# Wash_Hand.net
KiCad netlist of a schematic drawn in EAGLE
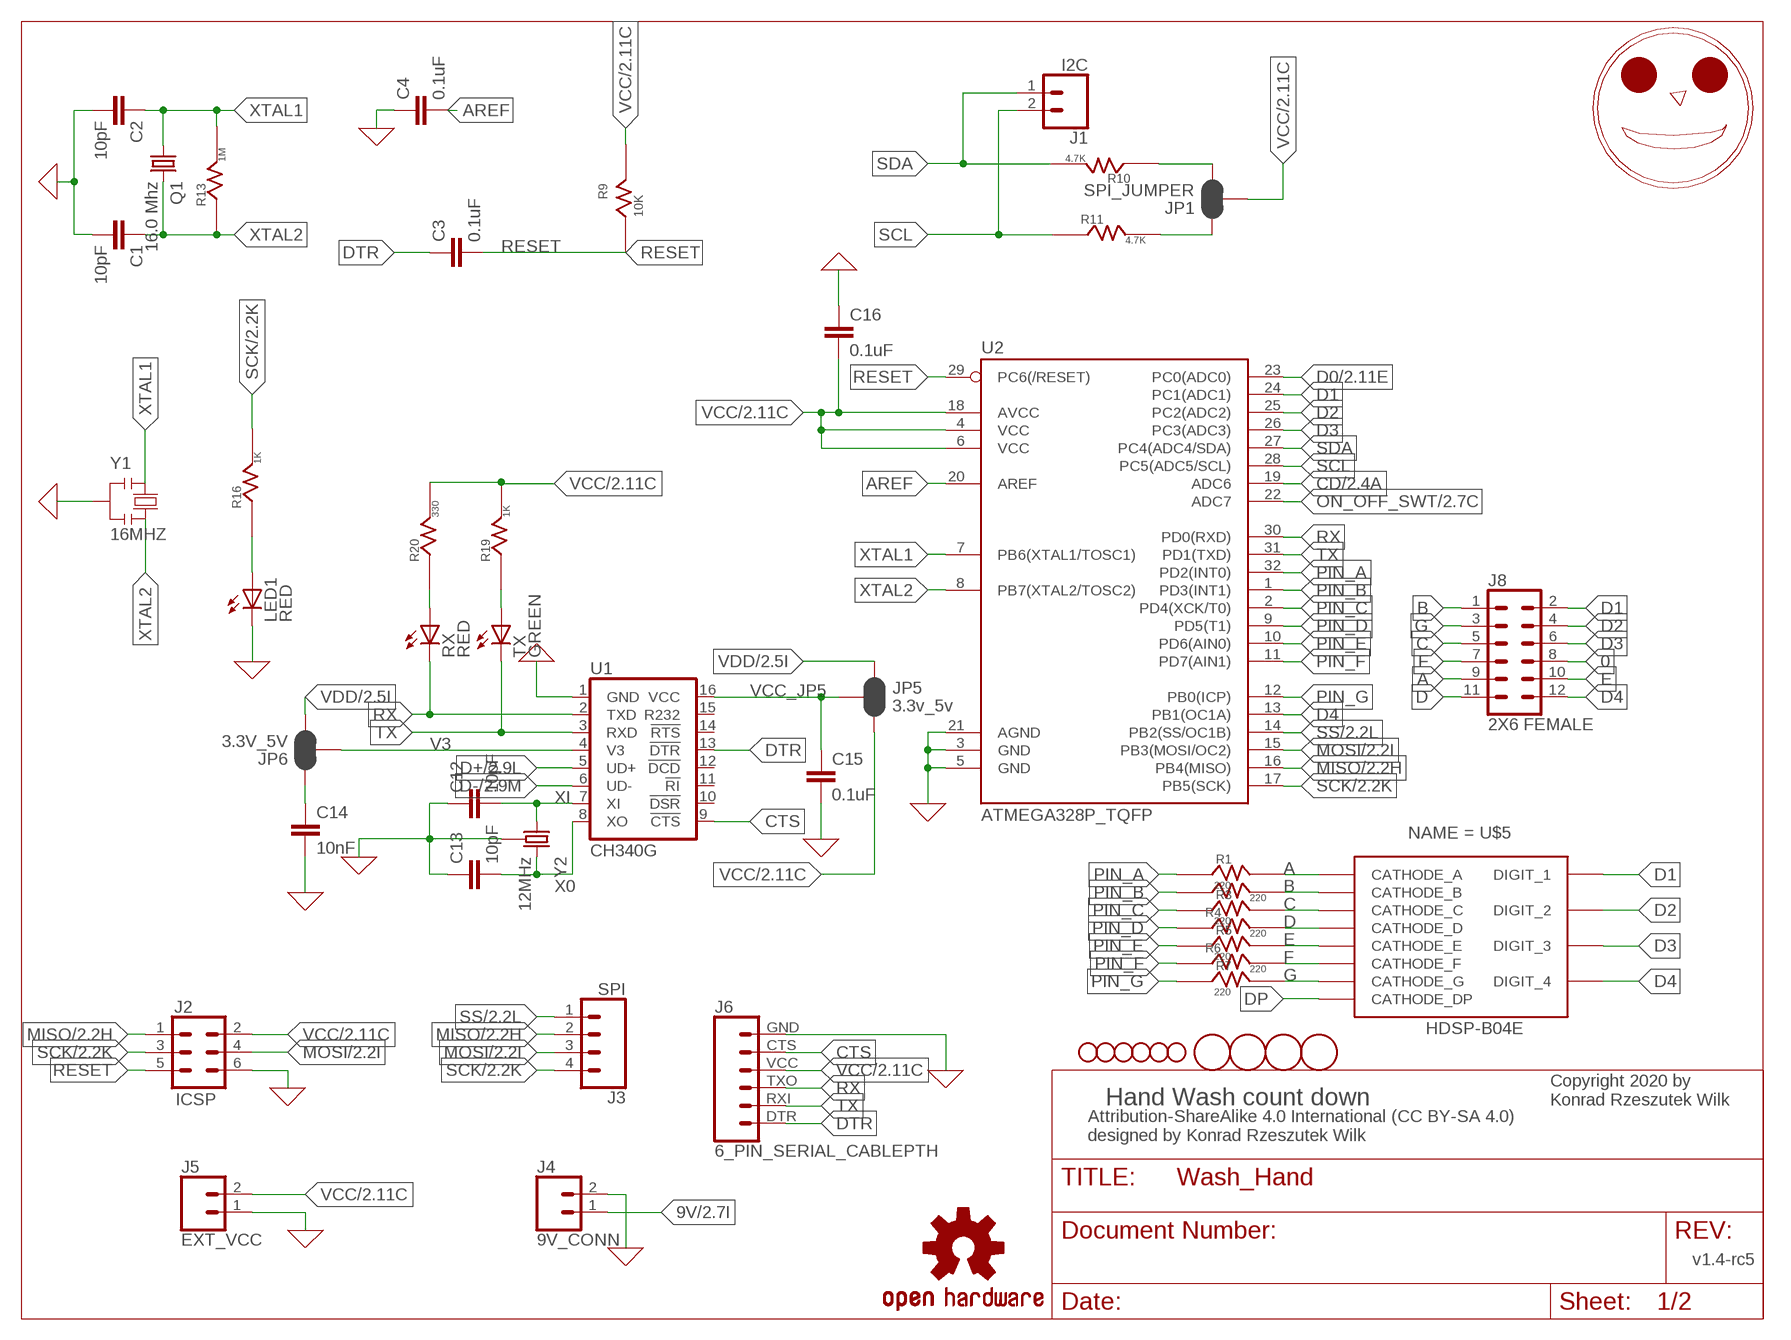
[diagram p0: schematic, sheet 1]
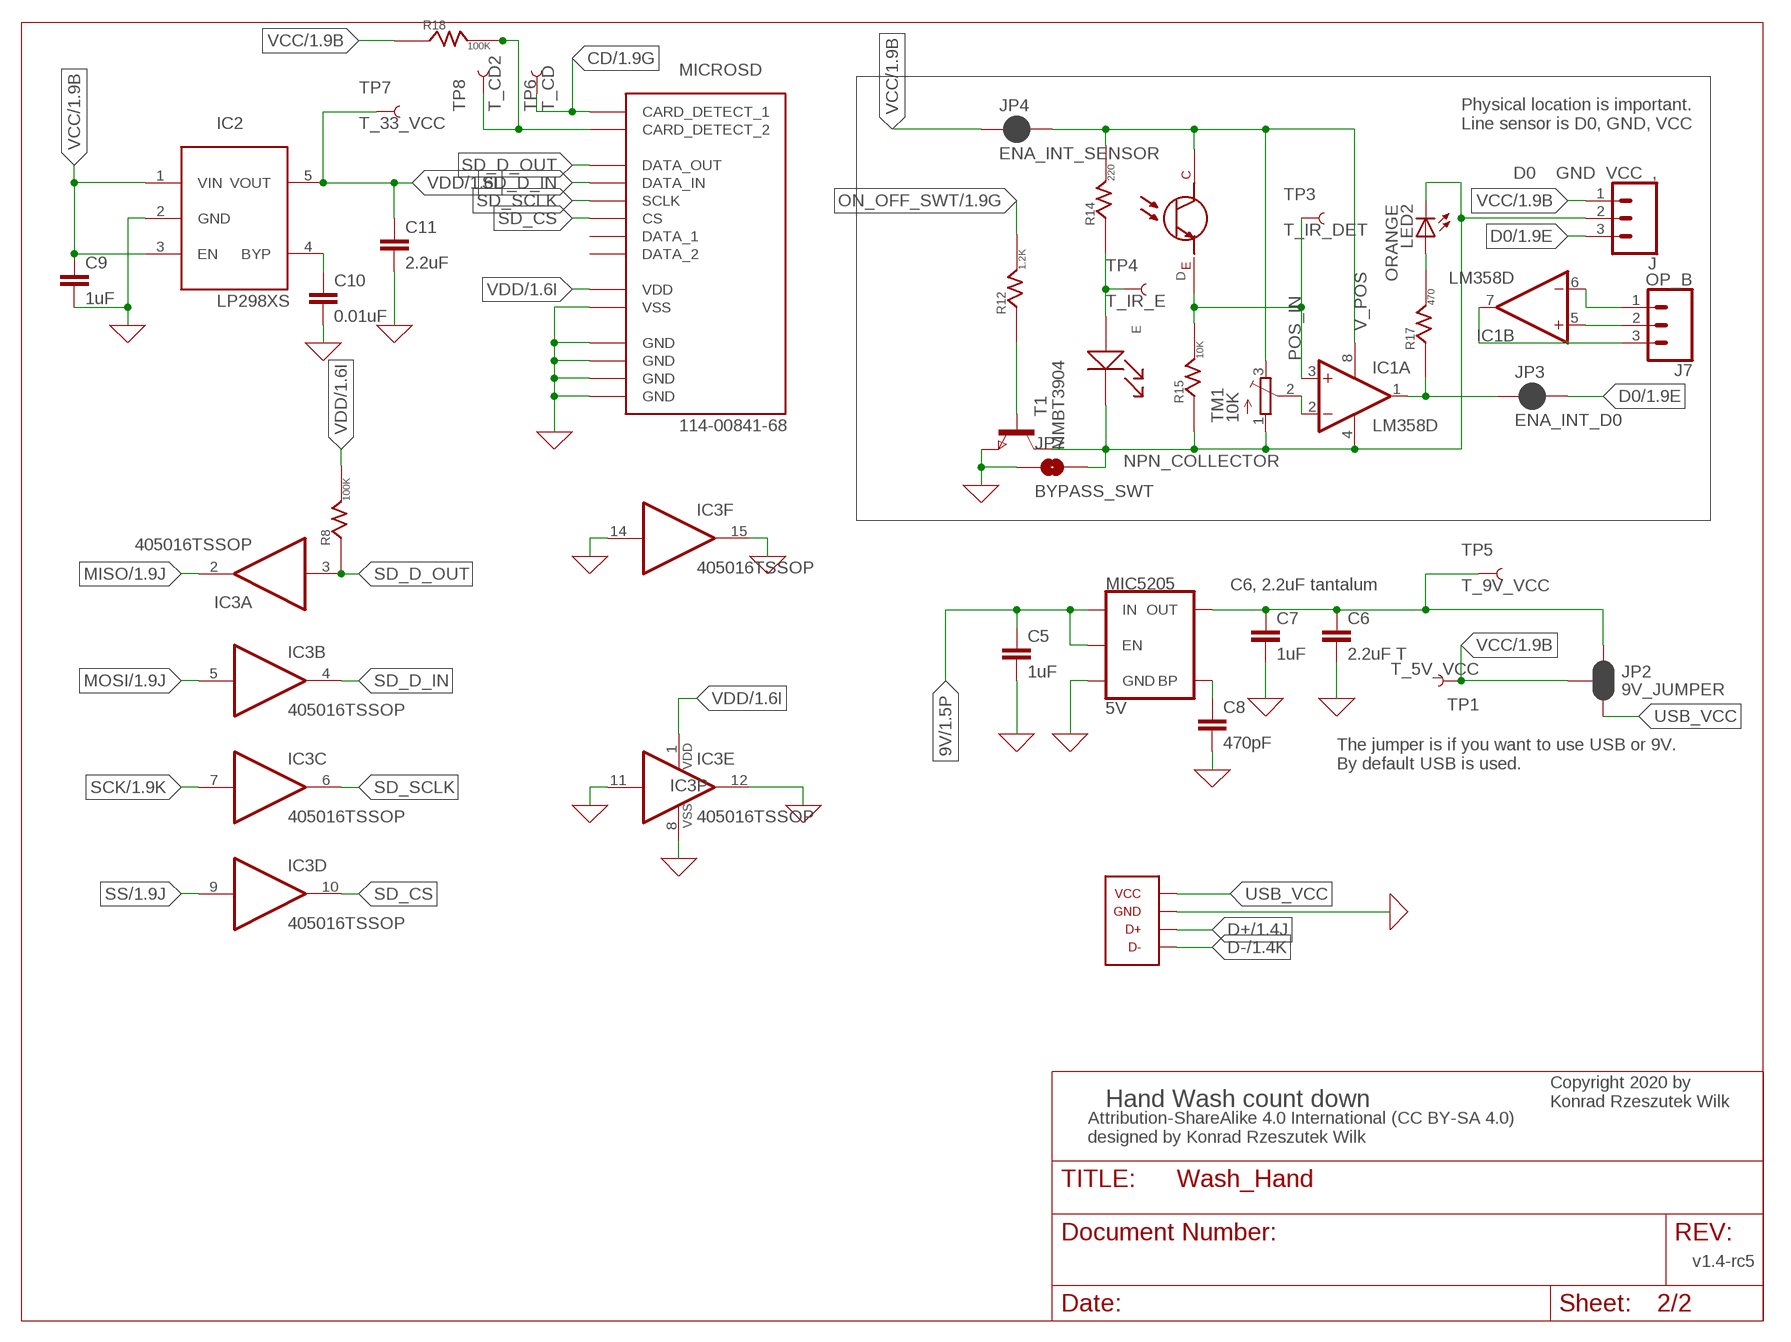
[diagram p1: schematic, sheet 2]

(export (version "E")
  (design (tool "Eeschema 10.0.6"))
  (components
    (comp (ref "C5")
      (value "1uF")
      (footprint "eagle-import:1206")
      (libsource (lib "eagle-import") (part "1.0UF-1206-50V-10%"))
    )
    (comp (ref "C6")
      (value "2.2uF T")
      (footprint "eagle-import:1206")
      (libsource (lib "eagle-import") (part "1.0UF-1206-50V-10%"))
    )
    (comp (ref "C7")
      (value "1uF")
      (footprint "eagle-import:1206")
      (libsource (lib "eagle-import") (part "1.0UF-1206-50V-10%"))
    )
    (comp (ref "C8")
      (value "470pF")
      (footprint "eagle-import:1206")
      (libsource (lib "eagle-import") (part "1.0UF-1206-50V-10%"))
    )
    (comp (ref "C9")
      (value "1uF")
      (footprint "eagle-import:1206")
      (libsource (lib "eagle-import") (part "1.0UF-1206-50V-10%"))
    )
    (comp (ref "C10")
      (value "0.01uF")
      (footprint "eagle-import:1206")
      (libsource (lib "eagle-import") (part "1.0UF-1206-50V-10%"))
    )
    (comp (ref "C11")
      (value "2.2uF")
      (footprint "eagle-import:1206")
      (libsource (lib "eagle-import") (part "1.0UF-1206-50V-10%"))
    )
    (comp (ref "D")
      (value "LTR-301")
      (footprint "eagle-import:LTR-301")
      (libsource (lib "eagle-import") (part "LTR-301"))
    )
    (comp (ref "E")
      (value "LTE-302")
      (footprint "eagle-import:LTE-302")
      (libsource (lib "eagle-import") (part "LTE-302"))
    )
    (comp (ref "IC1")
      (value "LM358D")
      (footprint "eagle-import:SO08")
      (libsource (lib "eagle-import") (part "LM358D"))
    )
    (comp (ref "IC2")
      (value "LP298XS")
      (footprint "eagle-import:SOT23-5L")
      (libsource (lib "eagle-import") (part "LP298XS"))
    )
    (comp (ref "IC3")
      (value "405016TSSOP")
      (footprint "eagle-import:TSSOP16")
      (libsource (lib "eagle-import") (part "405016TSSOP"))
    )
    (comp (ref "J")
      (value "D0 GND VCC ,")
      (footprint "eagle-import:1X03")
      (libsource (lib "eagle-import") (part "CONN_03"))
    )
    (comp (ref "J7")
      (value "OP_B")
      (footprint "eagle-import:1X03")
      (libsource (lib "eagle-import") (part "CONN_03"))
    )
    (comp (ref "JP2")
      (value "9V_JUMPER")
      (footprint "eagle-import:SMT-JUMPER_3_2-NC_PASTE_SILK")
      (libsource (lib "eagle-import") (part "JUMPER-SMT_3_2-NC_PASTE_SILK"))
    )
    (comp (ref "JP3")
      (value "ENA_INT_D0")
      (footprint "eagle-import:SMT-JUMPER_2_NC_PASTE_SILK")
      (libsource (lib "eagle-import") (part "JUMPER-SMT_2_NC_PASTE_SILK"))
    )
    (comp (ref "JP4")
      (value "ENA_INT_SENSOR")
      (footprint "eagle-import:SMT-JUMPER_2_NC_PASTE_SILK")
      (libsource (lib "eagle-import") (part "JUMPER-SMT_2_NC_PASTE_SILK"))
    )
    (comp (ref "JP7")
      (value "BYPASS_SWT")
      (footprint "eagle-import:SMT-JUMPER_2_NO_SILK")
      (libsource (lib "eagle-import") (part "JUMPER-SMT_2_NO_SILK"))
    )
    (comp (ref "LED2")
      (value "ORANGE")
      (footprint "eagle-import:1206")
      (libsource (lib "eagle-import") (part "LEDSMT1206"))
    )
    (comp (ref "MIC5205")
      (value "5V")
      (footprint "eagle-import:SOT23-5")
      (libsource (lib "eagle-import") (part "V_REG_MIC52055V"))
    )
    (comp (ref "MICROSD")
      (value "114-00841-68")
      (footprint "eagle-import:114-00841-68")
      (libsource (lib "eagle-import") (part "114-00841-68"))
    )
    (comp (ref "R8")
      (value "100K")
      (footprint "eagle-import:1206")
      (libsource (lib "eagle-import") (part "RESISTORR1206"))
    )
    (comp (ref "R12")
      (value "1.2K")
      (footprint "eagle-import:1206")
      (libsource (lib "eagle-import") (part "RESISTORR1206"))
    )
    (comp (ref "R14")
      (value "220")
      (footprint "eagle-import:1206")
      (libsource (lib "eagle-import") (part "RESISTORR1206"))
    )
    (comp (ref "R15")
      (value "10K")
      (footprint "eagle-import:1206")
      (libsource (lib "eagle-import") (part "RESISTORR1206"))
    )
    (comp (ref "R17")
      (value "470")
      (footprint "eagle-import:1206")
      (libsource (lib "eagle-import") (part "RESISTORR1206"))
    )
    (comp (ref "R18")
      (value "100K")
      (footprint "eagle-import:1206")
      (libsource (lib "eagle-import") (part "RESISTORR1206"))
    )
    (comp (ref "T1")
      (value "MMBT3904")
      (footprint "eagle-import:SOT-23")
      (fields (field (name "MPN") "DSS20201L-7"))
      (libsource (lib "eagle-import") (part "NPNSOT23"))
    )
    (comp (ref "TM1")
      (value "10K")
      (footprint "eagle-import:TC33X")
      (libsource (lib "eagle-import") (part "TRIMPOTTC33X"))
    )
    (comp (ref "TP1")
      (value "T_5V_VCC")
      (footprint "eagle-import:PAD.03X.04")
      (libsource (lib "eagle-import") (part "TEST-POINT3X4"))
    )
    (comp (ref "TP3")
      (value "T_IR_DET")
      (footprint "eagle-import:PAD.03X.04")
      (libsource (lib "eagle-import") (part "TEST-POINT3X4"))
    )
    (comp (ref "TP4")
      (value "T_IR_E")
      (footprint "eagle-import:PAD.03X.04")
      (libsource (lib "eagle-import") (part "TEST-POINT3X4"))
    )
    (comp (ref "TP5")
      (value "T_9V_VCC")
      (footprint "eagle-import:PAD.03X.04")
      (libsource (lib "eagle-import") (part "TEST-POINT3X4"))
    )
    (comp (ref "TP6")
      (value "T_CD")
      (footprint "eagle-import:PAD.03X.04")
      (libsource (lib "eagle-import") (part "TEST-POINT3X4"))
    )
    (comp (ref "TP7")
      (value "T_33_VCC")
      (footprint "eagle-import:PAD.03X.04")
      (libsource (lib "eagle-import") (part "TEST-POINT3X4"))
    )
    (comp (ref "TP8")
      (value "T_CD2")
      (footprint "eagle-import:PAD.03X.04")
      (libsource (lib "eagle-import") (part "TEST-POINT3X4"))
    )
    (comp (ref "U$4")
      (value "USB_MICROB_10118194_AMPHENOL")
      (footprint "eagle-import:USB_MICROB_10118194_AMPHENOL")
      (libsource (lib "eagle-import") (part "USB_MICROB_10118194_AMPHENOL"))
    )
    (comp (ref "C1")
      (value "10pF")
      (footprint "eagle-import:1206")
      (libsource (lib "eagle-import") (part "10UF-1206-6.3V-20%"))
    )
    (comp (ref "C2")
      (value "10pF")
      (footprint "eagle-import:1206")
      (libsource (lib "eagle-import") (part "10UF-1206-6.3V-20%"))
    )
    (comp (ref "C3")
      (value "0.1uF")
      (footprint "eagle-import:1206")
      (libsource (lib "eagle-import") (part "1.0UF-1206-50V-10%"))
    )
    (comp (ref "C4")
      (value "0.1uF")
      (footprint "eagle-import:1206")
      (libsource (lib "eagle-import") (part "1.0UF-1206-50V-10%"))
    )
    (comp (ref "C12")
      (value "10pF")
      (footprint "eagle-import:1206")
      (libsource (lib "eagle-import") (part "10UF-1206-6.3V-20%"))
    )
    (comp (ref "C13")
      (value "10pF")
      (footprint "eagle-import:1206")
      (libsource (lib "eagle-import") (part "10UF-1206-6.3V-20%"))
    )
    (comp (ref "C14")
      (value "10nF")
      (footprint "eagle-import:1206")
      (libsource (lib "eagle-import") (part "10UF-1206-6.3V-20%"))
    )
    (comp (ref "C15")
      (value "0.1uF")
      (footprint "eagle-import:1206")
      (libsource (lib "eagle-import") (part "10UF-1206-6.3V-20%"))
    )
    (comp (ref "C16")
      (value "0.1uF")
      (footprint "eagle-import:1206")
      (libsource (lib "eagle-import") (part "10UF-1206-6.3V-20%"))
    )
    (comp (ref "H1")
      (value "STAND-OFF")
      (footprint "eagle-import:STAND-OFF")
      (libsource (lib "eagle-import") (part "STAND-OFF"))
    )
    (comp (ref "H2")
      (value "STAND-OFF")
      (footprint "eagle-import:STAND-OFF")
      (libsource (lib "eagle-import") (part "STAND-OFF"))
    )
    (comp (ref "H3")
      (value "STAND-OFF")
      (footprint "eagle-import:STAND-OFF")
      (libsource (lib "eagle-import") (part "STAND-OFF"))
    )
    (comp (ref "H4")
      (value "STAND-OFF")
      (footprint "eagle-import:STAND-OFF")
      (libsource (lib "eagle-import") (part "STAND-OFF"))
    )
    (comp (ref "H5")
      (value "STAND-OFF")
      (footprint "eagle-import:STAND-OFF")
      (libsource (lib "eagle-import") (part "STAND-OFF"))
    )
    (comp (ref "H6")
      (value "STAND-OFF")
      (footprint "eagle-import:STAND-OFF")
      (libsource (lib "eagle-import") (part "STAND-OFF"))
    )
    (comp (ref "J1")
      (value "I2C")
      (footprint "eagle-import:1X02")
      (libsource (lib "eagle-import") (part "CONN_02"))
    )
    (comp (ref "J2")
      (value "ICSP")
      (footprint "eagle-import:2X3")
      (libsource (lib "eagle-import") (part "CONN_03X2FEMALE"))
    )
    (comp (ref "J3")
      (value "SPI")
      (footprint "eagle-import:1X04")
      (libsource (lib "eagle-import") (part "CONN_04"))
    )
    (comp (ref "J4")
      (value "9V_CONN")
      (footprint "eagle-import:1X02")
      (libsource (lib "eagle-import") (part "CONN_02"))
    )
    (comp (ref "J5")
      (value "EXT_VCC")
      (footprint "eagle-import:1X02")
      (libsource (lib "eagle-import") (part "CONN_02"))
    )
    (comp (ref "J6")
      (value "6_PIN_SERIAL_CABLEPTH")
      (footprint "eagle-import:FTDI_BASIC")
      (libsource (lib "eagle-import") (part "6_PIN_SERIAL_CABLEPTH"))
    )
    (comp (ref "J8")
      (value "2X6 FEMALE")
      (footprint "eagle-import:2X6")
      (libsource (lib "eagle-import") (part "CONN_06X2PTH_FEMALE"))
    )
    (comp (ref "JP1")
      (value "SPI_JUMPER")
      (footprint "eagle-import:SMT-JUMPER_3_2-NC_PASTE_SILK")
      (libsource (lib "eagle-import") (part "JUMPER-SMT_3_2-NC_PASTE_SILK"))
    )
    (comp (ref "JP5")
      (value "3.3v_5v")
      (footprint "eagle-import:SMT-JUMPER_3_2-NC_PASTE_SILK")
      (libsource (lib "eagle-import") (part "JUMPER-SMT_3_2-NC_PASTE_SILK"))
    )
    (comp (ref "JP6")
      (value "3.3V_5V")
      (footprint "eagle-import:SMT-JUMPER_3_2-NC_PASTE_SILK")
      (libsource (lib "eagle-import") (part "JUMPER-SMT_3_2-NC_PASTE_SILK"))
    )
    (comp (ref "LED1")
      (value "RED")
      (footprint "eagle-import:1206")
      (libsource (lib "eagle-import") (part "LEDSMT1206"))
    )
    (comp (ref "LOGO1")
      (value "OSHW-LOGOM")
      (footprint "eagle-import:OSHW-LOGO-M")
      (libsource (lib "eagle-import") (part "OSHW-LOGOM"))
    )
    (comp (ref "LOGO2")
      (value "HAPPY_FACE_LOGO")
      (footprint "eagle-import:HAPPY_FACE_LOGO")
      (libsource (lib "eagle-import") (part "HAPPY_FACE_LOGO"))
    )
    (comp (ref "Q1")
      (value "16.0 Mhz")
      (footprint "eagle-import:HC49_S")
      (libsource (lib "eagle-import") (part "CRYSTALHC49S"))
    )
    (comp (ref "R1")
      (value "220")
      (footprint "eagle-import:1206")
      (libsource (lib "eagle-import") (part "RESISTORR1206"))
    )
    (comp (ref "R2")
      (value "220")
      (footprint "eagle-import:1206")
      (libsource (lib "eagle-import") (part "RESISTORR1206"))
    )
    (comp (ref "R3")
      (value "220")
      (footprint "eagle-import:1206")
      (libsource (lib "eagle-import") (part "RESISTORR1206"))
    )
    (comp (ref "R4")
      (value "220")
      (footprint "eagle-import:1206")
      (libsource (lib "eagle-import") (part "RESISTORR1206"))
    )
    (comp (ref "R5")
      (value "220")
      (footprint "eagle-import:1206")
      (libsource (lib "eagle-import") (part "RESISTORR1206"))
    )
    (comp (ref "R6")
      (value "220")
      (footprint "eagle-import:1206")
      (libsource (lib "eagle-import") (part "RESISTORR1206"))
    )
    (comp (ref "R7")
      (value "220")
      (footprint "eagle-import:1206")
      (libsource (lib "eagle-import") (part "RESISTORR1206"))
    )
    (comp (ref "R9")
      (value "10K")
      (footprint "eagle-import:1206")
      (libsource (lib "eagle-import") (part "RESISTORR1206"))
    )
    (comp (ref "R10")
      (value "4.7K")
      (footprint "eagle-import:1206")
      (libsource (lib "eagle-import") (part "RESISTORR1206"))
    )
    (comp (ref "R11")
      (value "4.7K")
      (footprint "eagle-import:1206")
      (libsource (lib "eagle-import") (part "RESISTORR1206"))
    )
    (comp (ref "R13")
      (value "1M")
      (footprint "eagle-import:1206")
      (libsource (lib "eagle-import") (part "RESISTORR1206"))
    )
    (comp (ref "R16")
      (value "1K")
      (footprint "eagle-import:1206")
      (libsource (lib "eagle-import") (part "RESISTORR1206"))
    )
    (comp (ref "R19")
      (value "1K")
      (footprint "eagle-import:1206")
      (libsource (lib "eagle-import") (part "RESISTORR1206"))
    )
    (comp (ref "R20")
      (value "330")
      (footprint "eagle-import:1206")
      (libsource (lib "eagle-import") (part "RESISTORR1206"))
    )
    (comp (ref "RX")
      (value "RED")
      (footprint "eagle-import:1206")
      (libsource (lib "eagle-import") (part "LEDSMT1206"))
    )
    (comp (ref "TX")
      (value "GREEN")
      (footprint "eagle-import:1206")
      (libsource (lib "eagle-import") (part "LEDSMT1206"))
    )
    (comp (ref "U$5")
      (value "HDSP-B04E")
      (footprint "eagle-import:HDSP-B0XE")
      (libsource (lib "eagle-import") (part "HDSP-B04E"))
    )
    (comp (ref "U$7")
      (value "FIDUCIAL")
      (footprint "eagle-import:FIDUCIAL_1MM")
      (libsource (lib "eagle-import") (part "FIDUCIAL"))
    )
    (comp (ref "U$8")
      (value "FIDUCIAL")
      (footprint "eagle-import:FIDUCIAL_1MM")
      (libsource (lib "eagle-import") (part "FIDUCIAL"))
    )
    (comp (ref "U$9")
      (value "FIDUCIAL")
      (footprint "eagle-import:FIDUCIAL_1MM")
      (libsource (lib "eagle-import") (part "FIDUCIAL"))
    )
    (comp (ref "U$10")
      (value "FIDUCIAL")
      (footprint "eagle-import:FIDUCIAL_1MM")
      (libsource (lib "eagle-import") (part "FIDUCIAL"))
    )
    (comp (ref "U1")
      (value "CH340G")
      (footprint "eagle-import:SO016")
      (libsource (lib "eagle-import") (part "CH340GSMD"))
    )
    (comp (ref "U2")
      (value "ATMEGA328P_TQFP")
      (footprint "eagle-import:TQFP32-08")
      (libsource (lib "eagle-import") (part "ATMEGA328P_TQFP"))
    )
    (comp (ref "Y1")
      (value "16MHZ")
      (footprint "eagle-import:RESONATOR")
      (libsource (lib "eagle-import") (part "RESONATORMU"))
    )
    (comp (ref "Y2")
      (value "12MHz")
      (footprint "eagle-import:CRYSTAL-SMD-3.2X2.5")
      (libsource (lib "eagle-import") (part "CRYSTAL-GROUNDED3.2X2.5"))
    )
  )
  (nets
    (net (code "1") (name "0") (class "Default")
      (node (ref "C1") (pin "2") (pinfunction "2_2") (pintype "passive"))
      (node (ref "C10") (pin "2") (pinfunction "2_2") (pintype "passive"))
      (node (ref "C11") (pin "2") (pinfunction "2_2") (pintype "passive"))
      (node (ref "C12") (pin "1") (pinfunction "1_1") (pintype "passive"))
      (node (ref "C13") (pin "1") (pinfunction "1_1") (pintype "passive"))
      (node (ref "C14") (pin "2") (pinfunction "2_2") (pintype "passive"))
      (node (ref "C15") (pin "2") (pinfunction "2_2") (pintype "passive"))
      (node (ref "C16") (pin "1") (pinfunction "1_1") (pintype "passive"))
      (node (ref "C2") (pin "2") (pinfunction "2_2") (pintype "passive"))
      (node (ref "C4") (pin "1") (pinfunction "1_1") (pintype "passive"))
      (node (ref "C5") (pin "2") (pinfunction "2_2") (pintype "passive"))
      (node (ref "C6") (pin "2") (pinfunction "2_2") (pintype "passive"))
      (node (ref "C7") (pin "2") (pinfunction "2_2") (pintype "passive"))
      (node (ref "C8") (pin "2") (pinfunction "2_2") (pintype "passive"))
      (node (ref "C9") (pin "2") (pinfunction "2_2") (pintype "passive"))
      (node (ref "IC2") (pin "2") (pinfunction "GND_2") (pintype "bidirectional"))
      (node (ref "IC3") (pin "11") (pinfunction "I_11") (pintype "input"))
      (node (ref "IC3") (pin "12") (pinfunction "O_12") (pintype "output"))
      (node (ref "IC3") (pin "14") (pinfunction "I_14") (pintype "input"))
      (node (ref "IC3") (pin "15") (pinfunction "O_15") (pintype "output"))
      (node (ref "IC3") (pin "8") (pinfunction "VSS_8") (pintype "power_in"))
      (node (ref "J2") (pin "6") (pinfunction "6_6") (pintype "bidirectional"))
      (node (ref "J4") (pin "2") (pinfunction "2_2") (pintype "passive"))
      (node (ref "J5") (pin "1") (pinfunction "1_1") (pintype "passive"))
      (node (ref "J6") (pin "GND") (pinfunction "6_GND") (pintype "passive"))
      (node (ref "J8") (pin "8") (pinfunction "8_8") (pintype "passive"))
      (node (ref "JP7") (pin "1") (pinfunction "1_1") (pintype "passive"))
      (node (ref "LED1") (pin "C") (pinfunction "C_C") (pintype "passive"))
      (node (ref "MIC5205") (pin "2") (pinfunction "GND_2") (pintype "input"))
      (node (ref "MICROSD") (pin "GND$1") (pinfunction "GND_GND$1") (pintype "power_in"))
      (node (ref "MICROSD") (pin "GND$2") (pinfunction "GND_GND$2") (pintype "power_in"))
      (node (ref "MICROSD") (pin "GND$3") (pinfunction "GND_GND$3") (pintype "power_in"))
      (node (ref "MICROSD") (pin "GND$4") (pinfunction "GND_GND$4") (pintype "power_in"))
      (node (ref "MICROSD") (pin "VSS") (pinfunction "VSS_VSS") (pintype "power_in"))
      (node (ref "T1") (pin "2") (pinfunction "E_2") (pintype "passive"))
      (node (ref "U$4") (pin "5") (pinfunction "GND_5") (pintype "bidirectional"))
      (node (ref "U1") (pin "1") (pinfunction "GND_1") (pintype "bidirectional"))
      (node (ref "U2") (pin "21") (pinfunction "AGND_21") (pintype "bidirectional"))
      (node (ref "U2") (pin "3") (pinfunction "GND_3") (pintype "bidirectional"))
      (node (ref "U2") (pin "5") (pinfunction "GND_5") (pintype "bidirectional"))
      (node (ref "Y1") (pin "2") (pinfunction "2_2") (pintype "passive"))
      (node (ref "Y2") (pin "2") (pinfunction "GND_2") (pintype "passive"))
      (node (ref "Y2") (pin "4") (pinfunction "GND_4") (pintype "passive"))
    )
    (net (code "2") (name "9V") (class "Default")
      (node (ref "C5") (pin "1") (pinfunction "1_1") (pintype "passive"))
      (node (ref "J4") (pin "1") (pinfunction "1_1") (pintype "passive"))
      (node (ref "MIC5205") (pin "1") (pinfunction "IN_1") (pintype "input"))
      (node (ref "MIC5205") (pin "3") (pinfunction "EN_3") (pintype "input"))
    )
    (net (code "3") (name "A") (class "Default")
      (node (ref "J8") (pin "9") (pinfunction "9_9") (pintype "passive"))
      (node (ref "R1") (pin "2") (pinfunction "R_2_2") (pintype "bidirectional"))
      (node (ref "U$5") (pin "PIN$11") (pinfunction "CATHODE_A_PIN$11") (pintype "input"))
    )
    (net (code "4") (name "AREF") (class "Default")
      (node (ref "C4") (pin "2") (pinfunction "2_2") (pintype "passive"))
      (node (ref "U2") (pin "20") (pinfunction "AREF_20") (pintype "bidirectional"))
    )
    (net (code "5") (name "B") (class "Default")
      (node (ref "J8") (pin "1") (pinfunction "1_1") (pintype "passive"))
      (node (ref "R2") (pin "2") (pinfunction "R_2_2") (pintype "bidirectional"))
      (node (ref "U$5") (pin "PIN$7") (pinfunction "CATHODE_B_PIN$7") (pintype "input"))
    )
    (net (code "6") (name "C") (class "Default")
      (node (ref "J8") (pin "5") (pinfunction "5_5") (pintype "passive"))
      (node (ref "R3") (pin "2") (pinfunction "R_2_2") (pintype "bidirectional"))
      (node (ref "U$5") (pin "PIN$4") (pinfunction "CATHODE_C_PIN$4") (pintype "input"))
    )
    (net (code "7") (name "CD") (class "Default")
      (node (ref "MICROSD") (pin "CD_SW_1") (pinfunction "CARD_DETECT_1_CD_SW_1") (pintype "output"))
      (node (ref "TP6") (pin "P$1") (pinfunction "1_P$1") (pintype "bidirectional"))
      (node (ref "U2") (pin "19") (pinfunction "ADC6_19") (pintype "bidirectional"))
    )
    (net (code "8") (name "CTS") (class "Default")
      (node (ref "J6") (pin "CTS") (pinfunction "5_CTS") (pintype "passive"))
      (node (ref "U1") (pin "9") (pinfunction "~{CTS}_9") (pintype "bidirectional"))
    )
    (net (code "9") (name "D") (class "Default")
      (node (ref "J8") (pin "11") (pinfunction "11_11") (pintype "passive"))
      (node (ref "R4") (pin "2") (pinfunction "R_2_2") (pintype "bidirectional"))
      (node (ref "U$5") (pin "PIN$2") (pinfunction "CATHODE_D_PIN$2") (pintype "input"))
    )
    (net (code "10") (name "D+") (class "Default")
      (node (ref "U$4") (pin "3") (pinfunction "D+_3") (pintype "bidirectional"))
      (node (ref "U1") (pin "5") (pinfunction "UD+_5") (pintype "bidirectional"))
    )
    (net (code "11") (name "D-") (class "Default")
      (node (ref "U$4") (pin "2") (pinfunction "D-_2") (pintype "bidirectional"))
      (node (ref "U1") (pin "6") (pinfunction "UD-_6") (pintype "bidirectional"))
    )
    (net (code "12") (name "D0") (class "Default")
      (node (ref "IC1") (pin "1") (pinfunction "OUT_1") (pintype "output"))
      (node (ref "J") (pin "3") (pinfunction "3_3") (pintype "passive"))
      (node (ref "JP3") (pin "1") (pinfunction "1_1") (pintype "passive"))
      (node (ref "JP3") (pin "2") (pinfunction "2_2") (pintype "passive"))
      (node (ref "R17") (pin "1") (pinfunction "R_1_1") (pintype "bidirectional"))
      (node (ref "U2") (pin "23") (pinfunction "PC0(ADC0)_23") (pintype "bidirectional"))
    )
    (net (code "13") (name "D1") (class "Default")
      (node (ref "J8") (pin "2") (pinfunction "2_2") (pintype "passive"))
      (node (ref "U$5") (pin "PIN12") (pinfunction "DIGIT_1_PIN12") (pintype "input"))
      (node (ref "U2") (pin "24") (pinfunction "PC1(ADC1)_24") (pintype "bidirectional"))
    )
    (net (code "14") (name "D2") (class "Default")
      (node (ref "J8") (pin "4") (pinfunction "4_4") (pintype "passive"))
      (node (ref "U$5") (pin "PIN$9") (pinfunction "DIGIT_2_PIN$9") (pintype "input"))
      (node (ref "U2") (pin "25") (pinfunction "PC2(ADC2)_25") (pintype "bidirectional"))
    )
    (net (code "15") (name "D3") (class "Default")
      (node (ref "J8") (pin "6") (pinfunction "6_6") (pintype "passive"))
      (node (ref "U$5") (pin "PIN$8") (pinfunction "DIGIT_3_PIN$8") (pintype "input"))
      (node (ref "U2") (pin "26") (pinfunction "PC3(ADC3)_26") (pintype "bidirectional"))
    )
    (net (code "16") (name "D4") (class "Default")
      (node (ref "J8") (pin "12") (pinfunction "12_12") (pintype "passive"))
      (node (ref "U$5") (pin "PIN$6") (pinfunction "DIGIT_4_PIN$6") (pintype "input"))
      (node (ref "U2") (pin "13") (pinfunction "PB1(OC1A)_13") (pintype "bidirectional"))
    )
    (net (code "17") (name "DP") (class "Default")
      (node (ref "U$5") (pin "PIN$3") (pinfunction "CATHODE_DP_PIN$3") (pintype "input"))
    )
    (net (code "18") (name "DTR") (class "Default")
      (node (ref "C3") (pin "1") (pinfunction "1_1") (pintype "passive"))
      (node (ref "J6") (pin "DTR") (pinfunction "1_DTR") (pintype "passive"))
      (node (ref "U1") (pin "13") (pinfunction "~{DTR}_13") (pintype "bidirectional"))
    )
    (net (code "19") (name "E") (class "Default")
      (node (ref "J8") (pin "10") (pinfunction "10_10") (pintype "passive"))
      (node (ref "R5") (pin "2") (pinfunction "R_2_2") (pintype "bidirectional"))
      (node (ref "U$5") (pin "PIN$1") (pinfunction "CATHODE_E_PIN$1") (pintype "input"))
    )
    (net (code "20") (name "F") (class "Default")
      (node (ref "J8") (pin "7") (pinfunction "7_7") (pintype "passive"))
      (node (ref "R6") (pin "2") (pinfunction "R_2_2") (pintype "bidirectional"))
      (node (ref "U$5") (pin "PIN$10") (pinfunction "CATHODE_F_PIN$10") (pintype "input"))
    )
    (net (code "21") (name "G") (class "Default")
      (node (ref "J8") (pin "3") (pinfunction "3_3") (pintype "passive"))
      (node (ref "R7") (pin "2") (pinfunction "R_2_2") (pintype "bidirectional"))
      (node (ref "U$5") (pin "PIN$5") (pinfunction "CATHODE_G_PIN$5") (pintype "input"))
    )
    (net (code "22") (name "MISO") (class "Default")
      (node (ref "IC3") (pin "2") (pinfunction "O_2") (pintype "output"))
      (node (ref "J2") (pin "1") (pinfunction "1_1") (pintype "bidirectional"))
      (node (ref "J3") (pin "2") (pinfunction "2_2") (pintype "passive"))
      (node (ref "U2") (pin "16") (pinfunction "PB4(MISO)_16") (pintype "bidirectional"))
    )
    (net (code "23") (name "MOSI") (class "Default")
      (node (ref "IC3") (pin "5") (pinfunction "I_5") (pintype "input"))
      (node (ref "J2") (pin "4") (pinfunction "4_4") (pintype "bidirectional"))
      (node (ref "J3") (pin "3") (pinfunction "3_3") (pintype "passive"))
      (node (ref "U2") (pin "15") (pinfunction "PB3(MOSI/OC2)_15") (pintype "bidirectional"))
    )
    (net (code "24") (name "NPN_COLLECTOR") (class "Default")
      (node (ref "E") (pin "C") (pinfunction "K$1_C") (pintype "tri_state"))
      (node (ref "IC1") (pin "4") (pinfunction "V-_4") (pintype "power_in"))
      (node (ref "J") (pin "2") (pinfunction "2_2") (pintype "passive"))
      (node (ref "JP7") (pin "2") (pinfunction "2_2") (pintype "passive"))
      (node (ref "LED2") (pin "C") (pinfunction "C_C") (pintype "passive"))
      (node (ref "R15") (pin "1") (pinfunction "R_1_1") (pintype "bidirectional"))
      (node (ref "T1") (pin "1") (pinfunction "C_1") (pintype "passive"))
      (node (ref "TM1") (pin "1") (pinfunction "A_1") (pintype "passive"))
    )
    (net (code "25") (name "Net-(C14-Pad1)") (class "Default")
      (node (ref "C14") (pin "1") (pinfunction "1_1") (pintype "passive"))
      (node (ref "JP6") (pin "1") (pinfunction "1_1") (pintype "passive"))
    )
    (net (code "26") (name "Net-(E-A$1)") (class "Default")
      (node (ref "E") (pin "A") (pinfunction "A$1_A") (pintype "bidirectional"))
      (node (ref "R14") (pin "1") (pinfunction "R_1_1") (pintype "bidirectional"))
      (node (ref "TP4") (pin "P$1") (pinfunction "1_P$1") (pintype "bidirectional"))
    )
    (net (code "27") (name "Net-(IC1A--IN)") (class "Default")
      (node (ref "IC1") (pin "2") (pinfunction "-IN_2") (pintype "input"))
      (node (ref "TM1") (pin "2") (pinfunction "S_2") (pintype "passive"))
    )
    (net (code "28") (name "Net-(IC1B-+IN)") (class "Default")
      (node (ref "IC1") (pin "5") (pinfunction "+IN_5") (pintype "input"))
      (node (ref "J7") (pin "2") (pinfunction "2_2") (pintype "passive"))
    )
    (net (code "29") (name "Net-(IC1B--IN)") (class "Default")
      (node (ref "IC1") (pin "6") (pinfunction "-IN_6") (pintype "input"))
      (node (ref "J7") (pin "1") (pinfunction "1_1") (pintype "passive"))
    )
    (net (code "30") (name "Net-(IC1B-OUT)") (class "Default")
      (node (ref "IC1") (pin "7") (pinfunction "OUT_7") (pintype "output"))
      (node (ref "J7") (pin "3") (pinfunction "3_3") (pintype "passive"))
    )
    (net (code "31") (name "Net-(IC2-BYP)") (class "Default")
      (node (ref "C10") (pin "1") (pinfunction "1_1") (pintype "passive"))
      (node (ref "IC2") (pin "4") (pinfunction "BYP_4") (pintype "bidirectional"))
    )
    (net (code "32") (name "Net-(MIC5205-BP)") (class "Default")
      (node (ref "C8") (pin "1") (pinfunction "1_1") (pintype "passive"))
      (node (ref "MIC5205") (pin "4") (pinfunction "BP_4") (pintype "input"))
    )
    (net (code "33") (name "Net-(MIC5205-OUT)") (class "Default")
      (node (ref "C6") (pin "1") (pinfunction "1_1") (pintype "passive"))
      (node (ref "C7") (pin "1") (pinfunction "1_1") (pintype "passive"))
      (node (ref "JP2") (pin "1") (pinfunction "1_1") (pintype "passive"))
      (node (ref "MIC5205") (pin "5") (pinfunction "OUT_5") (pintype "passive"))
      (node (ref "TP5") (pin "P$1") (pinfunction "1_P$1") (pintype "bidirectional"))
    )
    (net (code "34") (name "Net-(MICROSD-CARD_DETECT_2)") (class "Default")
      (node (ref "MICROSD") (pin "CD_SW_2") (pinfunction "CARD_DETECT_2_CD_SW_2") (pintype "bidirectional"))
      (node (ref "R18") (pin "2") (pinfunction "R_2_2") (pintype "bidirectional"))
      (node (ref "TP8") (pin "P$1") (pinfunction "1_P$1") (pintype "bidirectional"))
    )
    (net (code "35") (name "Net-(R10-R_1)") (class "Default")
      (node (ref "JP1") (pin "3") (pinfunction "3_3") (pintype "passive"))
      (node (ref "R10") (pin "1") (pinfunction "R_1_1") (pintype "bidirectional"))
    )
    (net (code "36") (name "Net-(R11-R_2)") (class "Default")
      (node (ref "JP1") (pin "1") (pinfunction "1_1") (pintype "passive"))
      (node (ref "R11") (pin "2") (pinfunction "R_2_2") (pintype "bidirectional"))
    )
    (net (code "37") (name "Net-(R12-R_1)") (class "Default")
      (node (ref "R12") (pin "1") (pinfunction "R_1_1") (pintype "bidirectional"))
      (node (ref "T1") (pin "3") (pinfunction "B_3") (pintype "passive"))
    )
    (net (code "38") (name "Net-(R16-R_1)") (class "Default")
      (node (ref "LED1") (pin "A") (pinfunction "A_A") (pintype "passive"))
      (node (ref "R16") (pin "1") (pinfunction "R_1_1") (pintype "bidirectional"))
    )
    (net (code "39") (name "Net-(R17-R_2)") (class "Default")
      (node (ref "LED2") (pin "A") (pinfunction "A_A") (pintype "passive"))
      (node (ref "R17") (pin "2") (pinfunction "R_2_2") (pintype "bidirectional"))
    )
    (net (code "40") (name "Net-(R19-R_1)") (class "Default")
      (node (ref "R19") (pin "1") (pinfunction "R_1_1") (pintype "bidirectional"))
      (node (ref "TX") (pin "A") (pinfunction "A_A") (pintype "passive"))
    )
    (net (code "41") (name "Net-(R20-R_1)") (class "Default")
      (node (ref "R20") (pin "1") (pinfunction "R_1_1") (pintype "bidirectional"))
      (node (ref "RX") (pin "A") (pinfunction "A_A") (pintype "passive"))
    )
    (net (code "42") (name "ON_OFF_SWT") (class "Default")
      (node (ref "R12") (pin "2") (pinfunction "R_2_2") (pintype "bidirectional"))
      (node (ref "U2") (pin "22") (pinfunction "ADC7_22") (pintype "bidirectional"))
    )
    (net (code "43") (name "PIN_A") (class "Default")
      (node (ref "R1") (pin "1") (pinfunction "R_1_1") (pintype "bidirectional"))
      (node (ref "U2") (pin "32") (pinfunction "PD2(INT0)_32") (pintype "bidirectional"))
    )
    (net (code "44") (name "PIN_B") (class "Default")
      (node (ref "R2") (pin "1") (pinfunction "R_1_1") (pintype "bidirectional"))
      (node (ref "U2") (pin "1") (pinfunction "PD3(INT1)_1") (pintype "bidirectional"))
    )
    (net (code "45") (name "PIN_C") (class "Default")
      (node (ref "R3") (pin "1") (pinfunction "R_1_1") (pintype "bidirectional"))
      (node (ref "U2") (pin "2") (pinfunction "PD4(XCK/T0)_2") (pintype "bidirectional"))
    )
    (net (code "46") (name "PIN_D") (class "Default")
      (node (ref "R4") (pin "1") (pinfunction "R_1_1") (pintype "bidirectional"))
      (node (ref "U2") (pin "9") (pinfunction "PD5(T1)_9") (pintype "bidirectional"))
    )
    (net (code "47") (name "PIN_E") (class "Default")
      (node (ref "R5") (pin "1") (pinfunction "R_1_1") (pintype "bidirectional"))
      (node (ref "U2") (pin "10") (pinfunction "PD6(AIN0)_10") (pintype "bidirectional"))
    )
    (net (code "48") (name "PIN_F") (class "Default")
      (node (ref "R6") (pin "1") (pinfunction "R_1_1") (pintype "bidirectional"))
      (node (ref "U2") (pin "11") (pinfunction "PD7(AIN1)_11") (pintype "bidirectional"))
    )
    (net (code "49") (name "PIN_G") (class "Default")
      (node (ref "R7") (pin "1") (pinfunction "R_1_1") (pintype "bidirectional"))
      (node (ref "U2") (pin "12") (pinfunction "PB0(ICP)_12") (pintype "bidirectional"))
    )
    (net (code "50") (name "POS_IN") (class "Default")
      (node (ref "D") (pin "E") (pinfunction "E$1_E") (pintype "input"))
      (node (ref "IC1") (pin "3") (pinfunction "+IN_3") (pintype "input"))
      (node (ref "R15") (pin "2") (pinfunction "R_2_2") (pintype "bidirectional"))
      (node (ref "TP3") (pin "P$1") (pinfunction "1_P$1") (pintype "bidirectional"))
    )
    (net (code "51") (name "RESET") (class "Default")
      (node (ref "C3") (pin "2") (pinfunction "2_2") (pintype "passive"))
      (node (ref "J2") (pin "5") (pinfunction "5_5") (pintype "bidirectional"))
      (node (ref "R9") (pin "1") (pinfunction "R_1_1") (pintype "bidirectional"))
      (node (ref "U2") (pin "29") (pinfunction "PC6(/RESET)_29") (pintype "bidirectional"))
    )
    (net (code "52") (name "RX") (class "Default")
      (node (ref "J6") (pin "TXO") (pinfunction "3_TXO") (pintype "passive"))
      (node (ref "RX") (pin "C") (pinfunction "C_C") (pintype "passive"))
      (node (ref "U1") (pin "2") (pinfunction "TXD_2") (pintype "bidirectional"))
      (node (ref "U2") (pin "30") (pinfunction "PD0(RXD)_30") (pintype "bidirectional"))
    )
    (net (code "53") (name "SCK") (class "Default")
      (node (ref "IC3") (pin "7") (pinfunction "I_7") (pintype "input"))
      (node (ref "J2") (pin "3") (pinfunction "3_3") (pintype "bidirectional"))
      (node (ref "J3") (pin "4") (pinfunction "4_4") (pintype "passive"))
      (node (ref "R16") (pin "2") (pinfunction "R_2_2") (pintype "bidirectional"))
      (node (ref "U2") (pin "17") (pinfunction "PB5(SCK)_17") (pintype "bidirectional"))
    )
    (net (code "54") (name "SCL") (class "Default")
      (node (ref "J1") (pin "2") (pinfunction "2_2") (pintype "passive"))
      (node (ref "R11") (pin "1") (pinfunction "R_1_1") (pintype "bidirectional"))
      (node (ref "U2") (pin "28") (pinfunction "PC5(ADC5/SCL)_28") (pintype "bidirectional"))
    )
    (net (code "55") (name "SDA") (class "Default")
      (node (ref "J1") (pin "1") (pinfunction "1_1") (pintype "passive"))
      (node (ref "R10") (pin "2") (pinfunction "R_2_2") (pintype "bidirectional"))
      (node (ref "U2") (pin "27") (pinfunction "PC4(ADC4/SDA)_27") (pintype "bidirectional"))
    )
    (net (code "56") (name "SD_CS") (class "Default")
      (node (ref "IC3") (pin "10") (pinfunction "O_10") (pintype "output"))
      (node (ref "MICROSD") (pin "CS") (pinfunction "CS_CS") (pintype "bidirectional"))
    )
    (net (code "57") (name "SD_D_IN") (class "Default")
      (node (ref "IC3") (pin "4") (pinfunction "O_4") (pintype "output"))
      (node (ref "MICROSD") (pin "DATA_IN") (pinfunction "DATA_IN_DATA_IN") (pintype "bidirectional"))
    )
    (net (code "58") (name "SD_D_OUT") (class "Default")
      (node (ref "IC3") (pin "3") (pinfunction "I_3") (pintype "input"))
      (node (ref "MICROSD") (pin "DATA_OUT") (pinfunction "DATA_OUT_DATA_OUT") (pintype "bidirectional"))
      (node (ref "R8") (pin "1") (pinfunction "R_1_1") (pintype "bidirectional"))
    )
    (net (code "59") (name "SD_SCLK") (class "Default")
      (node (ref "IC3") (pin "6") (pinfunction "O_6") (pintype "output"))
      (node (ref "MICROSD") (pin "SCLK") (pinfunction "SCLK_SCLK") (pintype "bidirectional"))
    )
    (net (code "60") (name "SS") (class "Default")
      (node (ref "IC3") (pin "9") (pinfunction "I_9") (pintype "input"))
      (node (ref "J3") (pin "1") (pinfunction "1_1") (pintype "passive"))
      (node (ref "U2") (pin "14") (pinfunction "PB2(SS/OC1B)_14") (pintype "bidirectional"))
    )
    (net (code "61") (name "TX") (class "Default")
      (node (ref "J6") (pin "RXI") (pinfunction "2_RXI") (pintype "passive"))
      (node (ref "TX") (pin "C") (pinfunction "C_C") (pintype "passive"))
      (node (ref "U1") (pin "3") (pinfunction "RXD_3") (pintype "bidirectional"))
      (node (ref "U2") (pin "31") (pinfunction "PD1(TXD)_31") (pintype "bidirectional"))
    )
    (net (code "62") (name "USB_VCC") (class "Default")
      (node (ref "JP2") (pin "3") (pinfunction "3_3") (pintype "passive"))
      (node (ref "U$4") (pin "1") (pinfunction "VCC_1") (pintype "bidirectional"))
    )
    (net (code "63") (name "V3") (class "Default")
      (node (ref "JP6") (pin "2") (pinfunction "2_2") (pintype "passive"))
      (node (ref "U1") (pin "4") (pinfunction "V3_4") (pintype "bidirectional"))
    )
    (net (code "64") (name "VCC") (class "Default")
      (node (ref "C16") (pin "2") (pinfunction "2_2") (pintype "passive"))
      (node (ref "C9") (pin "1") (pinfunction "1_1") (pintype "passive"))
      (node (ref "IC2") (pin "1") (pinfunction "VIN_1") (pintype "bidirectional"))
      (node (ref "IC2") (pin "3") (pinfunction "EN_3") (pintype "bidirectional"))
      (node (ref "J") (pin "1") (pinfunction "1_1") (pintype "passive"))
      (node (ref "J2") (pin "2") (pinfunction "2_2") (pintype "bidirectional"))
      (node (ref "J5") (pin "2") (pinfunction "2_2") (pintype "passive"))
      (node (ref "J6") (pin "VCC") (pinfunction "4_VCC") (pintype "passive"))
      (node (ref "JP1") (pin "2") (pinfunction "2_2") (pintype "passive"))
      (node (ref "JP2") (pin "2") (pinfunction "2_2") (pintype "passive"))
      (node (ref "JP4") (pin "1") (pinfunction "1_1") (pintype "passive"))
      (node (ref "JP5") (pin "3") (pinfunction "3_3") (pintype "passive"))
      (node (ref "R18") (pin "1") (pinfunction "R_1_1") (pintype "bidirectional"))
      (node (ref "R19") (pin "2") (pinfunction "R_2_2") (pintype "bidirectional"))
      (node (ref "R20") (pin "2") (pinfunction "R_2_2") (pintype "bidirectional"))
      (node (ref "R9") (pin "2") (pinfunction "R_2_2") (pintype "bidirectional"))
      (node (ref "TP1") (pin "P$1") (pinfunction "1_P$1") (pintype "bidirectional"))
      (node (ref "U2") (pin "18") (pinfunction "AVCC_18") (pintype "bidirectional"))
      (node (ref "U2") (pin "4") (pinfunction "VCC_4") (pintype "bidirectional"))
      (node (ref "U2") (pin "6") (pinfunction "VCC_6") (pintype "bidirectional"))
    )
    (net (code "65") (name "VCC_JP5") (class "Default")
      (node (ref "C15") (pin "1") (pinfunction "1_1") (pintype "passive"))
      (node (ref "JP5") (pin "2") (pinfunction "2_2") (pintype "passive"))
      (node (ref "U1") (pin "16") (pinfunction "VCC_16") (pintype "bidirectional"))
    )
    (net (code "66") (name "VDD") (class "Default")
      (node (ref "C11") (pin "1") (pinfunction "1_1") (pintype "passive"))
      (node (ref "IC2") (pin "5") (pinfunction "VOUT_5") (pintype "bidirectional"))
      (node (ref "IC3") (pin "1") (pinfunction "VDD_1") (pintype "power_in"))
      (node (ref "JP5") (pin "1") (pinfunction "1_1") (pintype "passive"))
      (node (ref "JP6") (pin "3") (pinfunction "3_3") (pintype "passive"))
      (node (ref "MICROSD") (pin "VDD") (pinfunction "VDD_VDD") (pintype "power_in"))
      (node (ref "R8") (pin "2") (pinfunction "R_2_2") (pintype "bidirectional"))
      (node (ref "TP7") (pin "P$1") (pinfunction "1_P$1") (pintype "bidirectional"))
    )
    (net (code "67") (name "V_POS") (class "Default")
      (node (ref "D") (pin "C") (pinfunction "C$1_C") (pintype "tri_state"))
      (node (ref "IC1") (pin "8") (pinfunction "V+_8") (pintype "power_in"))
      (node (ref "JP4") (pin "2") (pinfunction "2_2") (pintype "passive"))
      (node (ref "R14") (pin "2") (pinfunction "R_2_2") (pintype "bidirectional"))
      (node (ref "TM1") (pin "3") (pinfunction "E_3") (pintype "passive"))
    )
    (net (code "68") (name "X0") (class "Default")
      (node (ref "C13") (pin "2") (pinfunction "2_2") (pintype "passive"))
      (node (ref "U1") (pin "8") (pinfunction "XO_8") (pintype "bidirectional"))
      (node (ref "Y2") (pin "3") (pinfunction "2_3") (pintype "passive"))
    )
    (net (code "69") (name "XI") (class "Default")
      (node (ref "C12") (pin "2") (pinfunction "2_2") (pintype "passive"))
      (node (ref "U1") (pin "7") (pinfunction "XI_7") (pintype "bidirectional"))
      (node (ref "Y2") (pin "1") (pinfunction "1_1") (pintype "passive"))
    )
    (net (code "70") (name "XTAL1") (class "Default")
      (node (ref "C2") (pin "1") (pinfunction "1_1") (pintype "passive"))
      (node (ref "Q1") (pin "1") (pinfunction "1_1") (pintype "passive"))
      (node (ref "R13") (pin "2") (pinfunction "R_2_2") (pintype "bidirectional"))
      (node (ref "U2") (pin "7") (pinfunction "PB6(XTAL1/TOSC1)_7") (pintype "bidirectional"))
      (node (ref "Y1") (pin "1") (pinfunction "1_1") (pintype "passive"))
    )
    (net (code "71") (name "XTAL2") (class "Default")
      (node (ref "C1") (pin "1") (pinfunction "1_1") (pintype "passive"))
      (node (ref "Q1") (pin "2") (pinfunction "2_2") (pintype "passive"))
      (node (ref "R13") (pin "1") (pinfunction "R_1_1") (pintype "bidirectional"))
      (node (ref "U2") (pin "8") (pinfunction "PB7(XTAL2/TOSC2)_8") (pintype "bidirectional"))
      (node (ref "Y1") (pin "3") (pinfunction "3_3") (pintype "passive"))
    )
    (net (code "72") (name "unconnected-(MICROSD-PadDATA_1)") (class "Default")
      (node (ref "MICROSD") (pin "DATA_1") (pinfunction "DATA_1_DATA_1") (pintype "bidirectional"))
    )
    (net (code "73") (name "unconnected-(MICROSD-PadDATA_2)") (class "Default")
      (node (ref "MICROSD") (pin "DATA_2") (pinfunction "DATA_2_DATA_2") (pintype "bidirectional"))
    )
    (net (code "74") (name "unconnected-(U1-R232-Pad15)") (class "Default")
      (node (ref "U1") (pin "15") (pinfunction "R232_15") (pintype "bidirectional"))
    )
    (net (code "75") (name "unconnected-(U1-~{DCD}-Pad12)") (class "Default")
      (node (ref "U1") (pin "12") (pinfunction "~{DCD}_12") (pintype "bidirectional"))
    )
    (net (code "76") (name "unconnected-(U1-~{DSR}-Pad10)") (class "Default")
      (node (ref "U1") (pin "10") (pinfunction "~{DSR}_10") (pintype "bidirectional"))
    )
    (net (code "77") (name "unconnected-(U1-~{RI}-Pad11)") (class "Default")
      (node (ref "U1") (pin "11") (pinfunction "~{RI}_11") (pintype "bidirectional"))
    )
    (net (code "78") (name "unconnected-(U1-~{RTS}-Pad14)") (class "Default")
      (node (ref "U1") (pin "14") (pinfunction "~{RTS}_14") (pintype "bidirectional"))
    )
  )
)
